# driver_motor.net
KiCad netlist of a schematic drawn in EAGLE
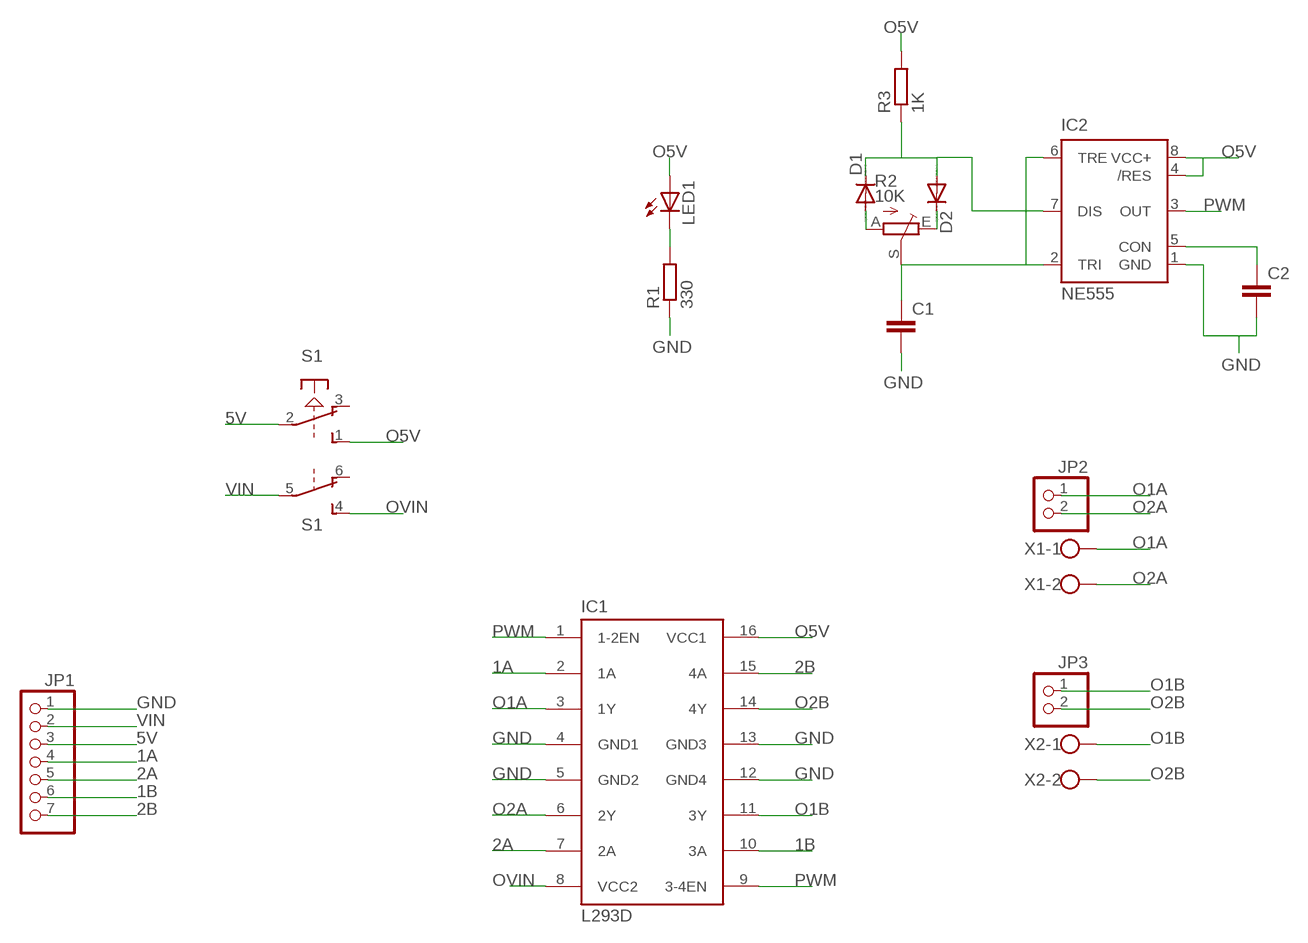
[diagram p0: schematic, sheet 1]

(export (version "E")
  (design (tool "Eeschema 10.0.6"))
  (components
    (comp (ref "C1")
      (value "C-EU050-035X075")
      (footprint "eagle-import:C050-035X075")
      (libsource (lib "eagle-import") (part "C-EU050-035X075"))
    )
    (comp (ref "C2")
      (value "C-EU050-035X075")
      (footprint "eagle-import:C050-035X075")
      (libsource (lib "eagle-import") (part "C-EU050-035X075"))
    )
    (comp (ref "D1")
      (value "1N4148DO35-7")
      (footprint "eagle-import:DO35-7")
      (libsource (lib "eagle-import") (part "1N4148DO35-7"))
    )
    (comp (ref "D2")
      (value "1N4148DO35-7")
      (footprint "eagle-import:DO35-7")
      (libsource (lib "eagle-import") (part "1N4148DO35-7"))
    )
    (comp (ref "IC1")
      (value "L293D")
      (footprint "eagle-import:DIL16")
      (libsource (lib "eagle-import") (part "L293D"))
    )
    (comp (ref "IC2")
      (value "NE555")
      (footprint "eagle-import:DIL-08")
      (fields (field (name "MF") "Arrow Electronics") (field (name "MPN") "NE555N"))
      (libsource (lib "eagle-import") (part "NE555"))
    )
    (comp (ref "JP1")
      (value "PINHD-1X7")
      (footprint "eagle-import:1X07")
      (libsource (lib "eagle-import") (part "PINHD-1X7"))
    )
    (comp (ref "JP2")
      (value "PINHD-1X2")
      (footprint "eagle-import:1X02")
      (libsource (lib "eagle-import") (part "PINHD-1X2"))
    )
    (comp (ref "JP3")
      (value "PINHD-1X2")
      (footprint "eagle-import:1X02")
      (libsource (lib "eagle-import") (part "PINHD-1X2"))
    )
    (comp (ref "LED1")
      (value "LED3MM")
      (footprint "eagle-import:LED3MM")
      (libsource (lib "eagle-import") (part "LED3MM"))
    )
    (comp (ref "R1")
      (value "330")
      (footprint "eagle-import:0207_7")
      (libsource (lib "eagle-import") (part "R-EU_0207/7"))
    )
    (comp (ref "R2")
      (value "10K")
      (footprint "eagle-import:CA6V")
      (libsource (lib "eagle-import") (part "TRIM_EU-CA6V"))
    )
    (comp (ref "R3")
      (value "1K")
      (footprint "eagle-import:0207_7")
      (libsource (lib "eagle-import") (part "R-EU_0207/7"))
    )
    (comp (ref "S1")
      (value "PVA2R")
      (footprint "eagle-import:PVA2R")
      (libsource (lib "eagle-import") (part "PVA2R"))
    )
    (comp (ref "X1")
      (value "W237-102")
      (footprint "eagle-import:W237-102")
      (fields (field (name "MPN") "237-102"))
      (libsource (lib "eagle-import") (part "W237-102"))
    )
    (comp (ref "X2")
      (value "W237-102")
      (footprint "eagle-import:W237-102")
      (fields (field (name "MPN") "237-102"))
      (libsource (lib "eagle-import") (part "W237-102"))
    )
  )
  (nets
    (net (code "1") (name "/1A") (class "Default")
      (node (ref "IC1") (pin "2") (pinfunction "1A_2") (pintype "input"))
      (node (ref "JP1") (pin "4") (pinfunction "4_4") (pintype "passive"))
    )
    (net (code "2") (name "/1B") (class "Default")
      (node (ref "IC1") (pin "10") (pinfunction "3A_10") (pintype "input"))
      (node (ref "JP1") (pin "6") (pinfunction "6_6") (pintype "passive"))
    )
    (net (code "3") (name "/2A") (class "Default")
      (node (ref "IC1") (pin "7") (pinfunction "2A_7") (pintype "input"))
      (node (ref "JP1") (pin "5") (pinfunction "5_5") (pintype "passive"))
    )
    (net (code "4") (name "/2B") (class "Default")
      (node (ref "IC1") (pin "15") (pinfunction "4A_15") (pintype "input"))
      (node (ref "JP1") (pin "7") (pinfunction "7_7") (pintype "passive"))
    )
    (net (code "5") (name "/5V") (class "Default")
      (node (ref "JP1") (pin "3") (pinfunction "3_3") (pintype "passive"))
      (node (ref "S1") (pin "2") (pinfunction "P_2") (pintype "passive"))
    )
    (net (code "6") (name "/GND") (class "Default")
      (node (ref "C1") (pin "2") (pinfunction "2_2") (pintype "passive"))
      (node (ref "C2") (pin "2") (pinfunction "2_2") (pintype "passive"))
      (node (ref "IC1") (pin "12") (pinfunction "GND4_12") (pintype "power_in"))
      (node (ref "IC1") (pin "13") (pinfunction "GND3_13") (pintype "power_in"))
      (node (ref "IC1") (pin "4") (pinfunction "GND1_4") (pintype "power_in"))
      (node (ref "IC1") (pin "5") (pinfunction "GND2_5") (pintype "power_in"))
      (node (ref "IC2") (pin "1") (pinfunction "GND_1") (pintype "power_in"))
      (node (ref "JP1") (pin "1") (pinfunction "1_1") (pintype "passive"))
      (node (ref "R1") (pin "1") (pinfunction "1_1") (pintype "passive"))
    )
    (net (code "7") (name "/O1A") (class "Default")
      (node (ref "IC1") (pin "3") (pinfunction "1Y_3") (pintype "output"))
      (node (ref "JP2") (pin "1") (pinfunction "1_1") (pintype "passive"))
      (node (ref "X1") (pin "1") (pinfunction "KL_1") (pintype "passive"))
    )
    (net (code "8") (name "/O1B") (class "Default")
      (node (ref "IC1") (pin "11") (pinfunction "3Y_11") (pintype "output"))
      (node (ref "JP3") (pin "1") (pinfunction "1_1") (pintype "passive"))
      (node (ref "X2") (pin "1") (pinfunction "KL_1") (pintype "passive"))
    )
    (net (code "9") (name "/O2A") (class "Default")
      (node (ref "IC1") (pin "6") (pinfunction "2Y_6") (pintype "output"))
      (node (ref "JP2") (pin "2") (pinfunction "2_2") (pintype "passive"))
      (node (ref "X1") (pin "2") (pinfunction "KL_2") (pintype "passive"))
    )
    (net (code "10") (name "/O2B") (class "Default")
      (node (ref "IC1") (pin "14") (pinfunction "4Y_14") (pintype "output"))
      (node (ref "JP3") (pin "2") (pinfunction "2_2") (pintype "passive"))
      (node (ref "X2") (pin "2") (pinfunction "KL_2") (pintype "passive"))
    )
    (net (code "11") (name "/O5V") (class "Default")
      (node (ref "IC1") (pin "16") (pinfunction "VCC1_16") (pintype "power_in"))
      (node (ref "IC2") (pin "4") (pinfunction "/RES_4") (pintype "input"))
      (node (ref "IC2") (pin "8") (pinfunction "VCC+_8") (pintype "power_in"))
      (node (ref "LED1") (pin "A") (pinfunction "A_A") (pintype "passive"))
      (node (ref "R3") (pin "2") (pinfunction "2_2") (pintype "passive"))
      (node (ref "S1") (pin "1") (pinfunction "S_1") (pintype "passive"))
    )
    (net (code "12") (name "/OVIN") (class "Default")
      (node (ref "IC1") (pin "8") (pinfunction "VCC2_8") (pintype "power_in"))
      (node (ref "S1") (pin "4") (pinfunction "S_4") (pintype "passive"))
    )
    (net (code "13") (name "/PWM") (class "Default")
      (node (ref "IC1") (pin "1") (pinfunction "1-2EN_1") (pintype "input"))
      (node (ref "IC1") (pin "9") (pinfunction "3-4EN_9") (pintype "input"))
      (node (ref "IC2") (pin "3") (pinfunction "OUT_3") (pintype "output"))
    )
    (net (code "14") (name "/VIN") (class "Default")
      (node (ref "JP1") (pin "2") (pinfunction "2_2") (pintype "passive"))
      (node (ref "S1") (pin "5") (pinfunction "P_5") (pintype "passive"))
    )
    (net (code "15") (name "Net-(D1-PadA)") (class "Default")
      (node (ref "D1") (pin "A") (pinfunction "A_A") (pintype "passive"))
      (node (ref "R2") (pin "A") (pinfunction "A_A") (pintype "passive"))
    )
    (net (code "16") (name "Net-(D2-PadC)") (class "Default")
      (node (ref "D2") (pin "C") (pinfunction "C_C") (pintype "passive"))
      (node (ref "R2") (pin "E") (pinfunction "E_E") (pintype "passive"))
    )
    (net (code "17") (name "Net-(IC2-CON)") (class "Default")
      (node (ref "C2") (pin "1") (pinfunction "1_1") (pintype "passive"))
      (node (ref "IC2") (pin "5") (pinfunction "CON_5") (pintype "input"))
    )
    (net (code "18") (name "Net-(IC2-DIS)") (class "Default")
      (node (ref "D1") (pin "C") (pinfunction "C_C") (pintype "passive"))
      (node (ref "D2") (pin "A") (pinfunction "A_A") (pintype "passive"))
      (node (ref "IC2") (pin "7") (pinfunction "DIS_7") (pintype "input"))
      (node (ref "R3") (pin "1") (pinfunction "1_1") (pintype "passive"))
    )
    (net (code "19") (name "Net-(IC2-TRE)") (class "Default")
      (node (ref "C1") (pin "1") (pinfunction "1_1") (pintype "passive"))
      (node (ref "IC2") (pin "2") (pinfunction "TRI_2") (pintype "input"))
      (node (ref "IC2") (pin "6") (pinfunction "TRE_6") (pintype "input"))
      (node (ref "R2") (pin "S") (pinfunction "S_S") (pintype "passive"))
    )
    (net (code "20") (name "Net-(LED1-C)") (class "Default")
      (node (ref "LED1") (pin "K") (pinfunction "C_K") (pintype "passive"))
      (node (ref "R1") (pin "2") (pinfunction "2_2") (pintype "passive"))
    )
    (net (code "21") (name "unconnected-(S1A-O-Pad3)") (class "Default")
      (node (ref "S1") (pin "3") (pinfunction "O_3") (pintype "passive"))
    )
    (net (code "22") (name "unconnected-(S1B-O-Pad6)") (class "Default")
      (node (ref "S1") (pin "6") (pinfunction "O_6") (pintype "passive"))
    )
  )
)
